# MOSFET_Board.net
KiCad netlist of a schematic drawn in EAGLE
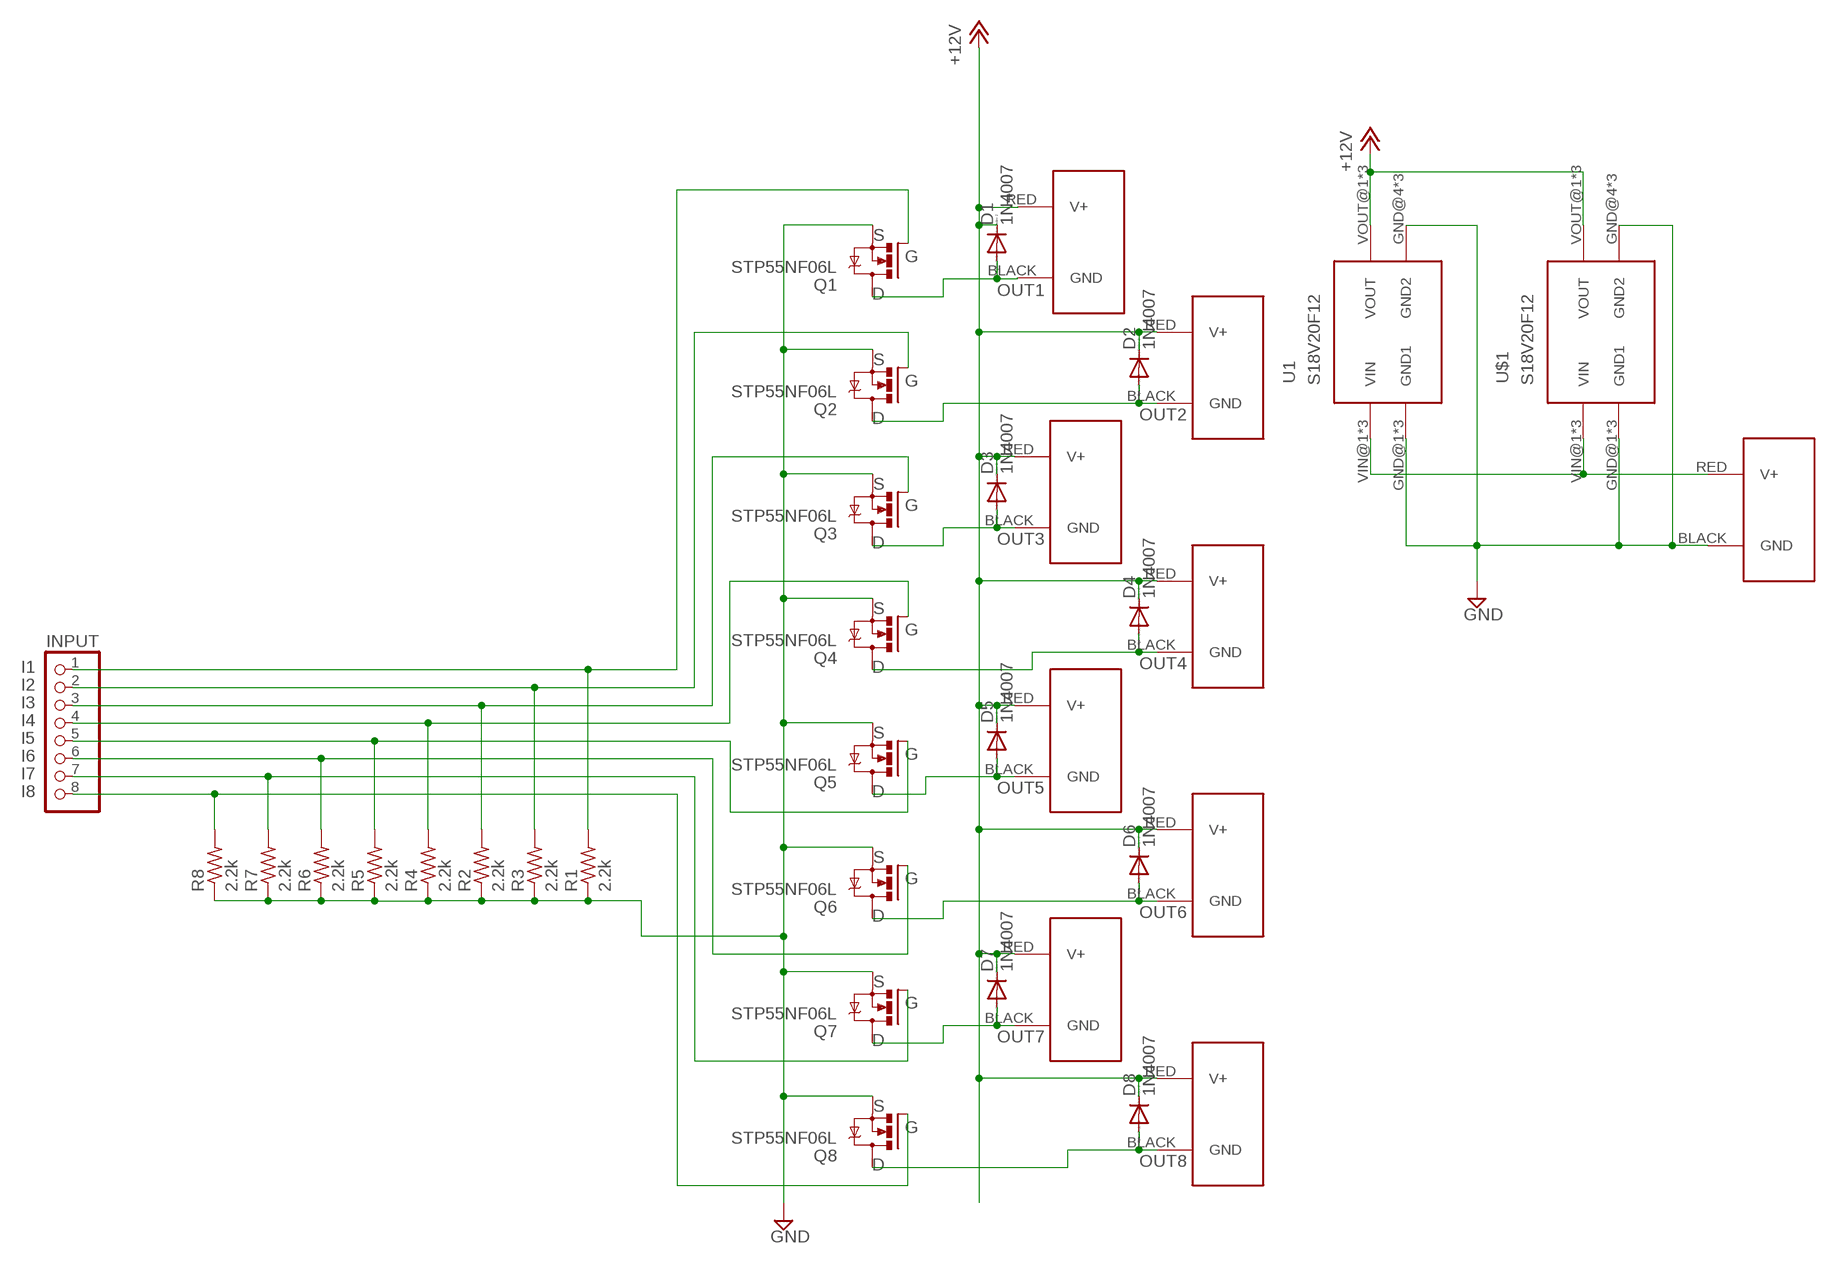
[diagram p0: schematic, sheet 1]

(export (version "E")
  (design (tool "Eeschema 10.0.6"))
  (components
    (comp (ref "D1")
      (value "1N4007")
      (footprint "eagle-import:DO41-10")
      (libsource (lib "eagle-import") (part "1N4007"))
    )
    (comp (ref "D2")
      (value "1N4007")
      (footprint "eagle-import:DO41-10")
      (libsource (lib "eagle-import") (part "1N4007"))
    )
    (comp (ref "D3")
      (value "1N4007")
      (footprint "eagle-import:DO41-10")
      (libsource (lib "eagle-import") (part "1N4007"))
    )
    (comp (ref "D4")
      (value "1N4007")
      (footprint "eagle-import:DO41-10")
      (libsource (lib "eagle-import") (part "1N4007"))
    )
    (comp (ref "D5")
      (value "1N4007")
      (footprint "eagle-import:DO41-10")
      (libsource (lib "eagle-import") (part "1N4007"))
    )
    (comp (ref "D6")
      (value "1N4007")
      (footprint "eagle-import:DO41-10")
      (libsource (lib "eagle-import") (part "1N4007"))
    )
    (comp (ref "D7")
      (value "1N4007")
      (footprint "eagle-import:DO41-10")
      (libsource (lib "eagle-import") (part "1N4007"))
    )
    (comp (ref "D8")
      (value "1N4007")
      (footprint "eagle-import:DO41-10")
      (libsource (lib "eagle-import") (part "1N4007"))
    )
    (comp (ref "INPUT")
      (value "PINHD-1X8")
      (footprint "eagle-import:1X08")
      (libsource (lib "eagle-import") (part "PINHD-1X8"))
    )
    (comp (ref "J1")
      (value "POWERPOLE_POWER25A")
      (footprint "eagle-import:POWERPOLE_PAIR_25A")
      (libsource (lib "eagle-import") (part "POWERPOLE_POWER25A"))
    )
    (comp (ref "J2")
      (value "POWERPOLE_POWER25A")
      (footprint "eagle-import:POWERPOLE_PAIR_25A")
      (libsource (lib "eagle-import") (part "POWERPOLE_POWER25A"))
    )
    (comp (ref "J3")
      (value "POWERPOLE_POWER25A")
      (footprint "eagle-import:POWERPOLE_PAIR_25A")
      (libsource (lib "eagle-import") (part "POWERPOLE_POWER25A"))
    )
    (comp (ref "J4")
      (value "POWERPOLE_POWER25A")
      (footprint "eagle-import:POWERPOLE_PAIR_25A")
      (libsource (lib "eagle-import") (part "POWERPOLE_POWER25A"))
    )
    (comp (ref "J5")
      (value "POWERPOLE_POWER25A")
      (footprint "eagle-import:POWERPOLE_PAIR_25A")
      (libsource (lib "eagle-import") (part "POWERPOLE_POWER25A"))
    )
    (comp (ref "J6")
      (value "POWERPOLE_POWER25A")
      (footprint "eagle-import:POWERPOLE_PAIR_25A")
      (libsource (lib "eagle-import") (part "POWERPOLE_POWER25A"))
    )
    (comp (ref "J7")
      (value "POWERPOLE_POWER25A")
      (footprint "eagle-import:POWERPOLE_PAIR_25A")
      (libsource (lib "eagle-import") (part "POWERPOLE_POWER25A"))
    )
    (comp (ref "J8")
      (value "POWERPOLE_POWER25A")
      (footprint "eagle-import:POWERPOLE_PAIR_25A")
      (libsource (lib "eagle-import") (part "POWERPOLE_POWER25A"))
    )
    (comp (ref "J9")
      (value "POWERPOLE_POWER25A")
      (footprint "eagle-import:POWERPOLE_PAIR_25A")
      (libsource (lib "eagle-import") (part "POWERPOLE_POWER25A"))
    )
    (comp (ref "Q1")
      (value "STP55NF06L")
      (footprint "eagle-import:TO220-3")
      (libsource (lib "eagle-import") (part "STP55NF06L"))
    )
    (comp (ref "Q2")
      (value "STP55NF06L")
      (footprint "eagle-import:TO220-3")
      (libsource (lib "eagle-import") (part "STP55NF06L"))
    )
    (comp (ref "Q3")
      (value "STP55NF06L")
      (footprint "eagle-import:TO220-3")
      (libsource (lib "eagle-import") (part "STP55NF06L"))
    )
    (comp (ref "Q4")
      (value "STP55NF06L")
      (footprint "eagle-import:TO220-3")
      (libsource (lib "eagle-import") (part "STP55NF06L"))
    )
    (comp (ref "Q5")
      (value "STP55NF06L")
      (footprint "eagle-import:TO220-3")
      (libsource (lib "eagle-import") (part "STP55NF06L"))
    )
    (comp (ref "Q6")
      (value "STP55NF06L")
      (footprint "eagle-import:TO220-3")
      (libsource (lib "eagle-import") (part "STP55NF06L"))
    )
    (comp (ref "Q7")
      (value "STP55NF06L")
      (footprint "eagle-import:TO220-3")
      (libsource (lib "eagle-import") (part "STP55NF06L"))
    )
    (comp (ref "Q8")
      (value "STP55NF06L")
      (footprint "eagle-import:TO220-3")
      (libsource (lib "eagle-import") (part "STP55NF06L"))
    )
    (comp (ref "R1")
      (value "2.2k")
      (footprint "eagle-import:0207_10")
      (libsource (lib "eagle-import") (part "R-US_0207/10"))
    )
    (comp (ref "R2")
      (value "2.2k")
      (footprint "eagle-import:0207_10")
      (libsource (lib "eagle-import") (part "R-US_0207/10"))
    )
    (comp (ref "R3")
      (value "2.2k")
      (footprint "eagle-import:0207_10")
      (libsource (lib "eagle-import") (part "R-US_0207/10"))
    )
    (comp (ref "R4")
      (value "2.2k")
      (footprint "eagle-import:0207_10")
      (libsource (lib "eagle-import") (part "R-US_0207/10"))
    )
    (comp (ref "R5")
      (value "2.2k")
      (footprint "eagle-import:0207_10")
      (libsource (lib "eagle-import") (part "R-US_0207/10"))
    )
    (comp (ref "R6")
      (value "2.2k")
      (footprint "eagle-import:0207_10")
      (libsource (lib "eagle-import") (part "R-US_0207/10"))
    )
    (comp (ref "R7")
      (value "2.2k")
      (footprint "eagle-import:0207_10")
      (libsource (lib "eagle-import") (part "R-US_0207/10"))
    )
    (comp (ref "R8")
      (value "2.2k")
      (footprint "eagle-import:0207_10")
      (libsource (lib "eagle-import") (part "R-US_0207/10"))
    )
    (comp (ref "U$1")
      (value "S18V20F12")
      (footprint "eagle-import:S18V20")
      (libsource (lib "eagle-import") (part "S18V20F12"))
    )
    (comp (ref "U1")
      (value "S18V20F12")
      (footprint "eagle-import:S18V20")
      (libsource (lib "eagle-import") (part "S18V20F12"))
    )
  )
  (nets
    (net (code "1") (name "+12V") (class "Default")
      (node (ref "D1") (pin "C") (pinfunction "C_C") (pintype "passive"))
      (node (ref "D2") (pin "C") (pinfunction "C_C") (pintype "passive"))
      (node (ref "D3") (pin "C") (pinfunction "C_C") (pintype "passive"))
      (node (ref "D4") (pin "C") (pinfunction "C_C") (pintype "passive"))
      (node (ref "D5") (pin "C") (pinfunction "C_C") (pintype "passive"))
      (node (ref "D6") (pin "C") (pinfunction "C_C") (pintype "passive"))
      (node (ref "D7") (pin "C") (pinfunction "C_C") (pintype "passive"))
      (node (ref "D8") (pin "C") (pinfunction "C_C") (pintype "passive"))
      (node (ref "J2") (pin "RED") (pinfunction "V+_RED") (pintype "power_in"))
      (node (ref "J3") (pin "RED") (pinfunction "V+_RED") (pintype "power_in"))
      (node (ref "J4") (pin "RED") (pinfunction "V+_RED") (pintype "power_in"))
      (node (ref "J5") (pin "RED") (pinfunction "V+_RED") (pintype "power_in"))
      (node (ref "J6") (pin "RED") (pinfunction "V+_RED") (pintype "power_in"))
      (node (ref "J7") (pin "RED") (pinfunction "V+_RED") (pintype "power_in"))
      (node (ref "J8") (pin "RED") (pinfunction "V+_RED") (pintype "power_in"))
      (node (ref "J9") (pin "RED") (pinfunction "V+_RED") (pintype "power_in"))
      (node (ref "U$1") (pin "VOUT@1") (pinfunction "VOUT_VOUT@1") (pintype "power_in"))
      (node (ref "U$1") (pin "VOUT@2") (pinfunction "VOUT_VOUT@2") (pintype "power_in"))
      (node (ref "U$1") (pin "VOUT@3") (pinfunction "VOUT_VOUT@3") (pintype "power_in"))
      (node (ref "U1") (pin "VOUT@1") (pinfunction "VOUT_VOUT@1") (pintype "power_in"))
      (node (ref "U1") (pin "VOUT@2") (pinfunction "VOUT_VOUT@2") (pintype "power_in"))
      (node (ref "U1") (pin "VOUT@3") (pinfunction "VOUT_VOUT@3") (pintype "power_in"))
    )
    (net (code "2") (name "/I1") (class "Default")
      (node (ref "INPUT") (pin "1") (pinfunction "1_1") (pintype "passive"))
      (node (ref "Q1") (pin "G") (pinfunction "G_G") (pintype "passive"))
      (node (ref "R1") (pin "2") (pinfunction "2_2") (pintype "passive"))
    )
    (net (code "3") (name "/I2") (class "Default")
      (node (ref "INPUT") (pin "2") (pinfunction "2_2") (pintype "passive"))
      (node (ref "Q2") (pin "G") (pinfunction "G_G") (pintype "passive"))
      (node (ref "R3") (pin "2") (pinfunction "2_2") (pintype "passive"))
    )
    (net (code "4") (name "/I3") (class "Default")
      (node (ref "INPUT") (pin "3") (pinfunction "3_3") (pintype "passive"))
      (node (ref "Q3") (pin "G") (pinfunction "G_G") (pintype "passive"))
      (node (ref "R2") (pin "2") (pinfunction "2_2") (pintype "passive"))
    )
    (net (code "5") (name "/I4") (class "Default")
      (node (ref "INPUT") (pin "4") (pinfunction "4_4") (pintype "passive"))
      (node (ref "Q4") (pin "G") (pinfunction "G_G") (pintype "passive"))
      (node (ref "R4") (pin "2") (pinfunction "2_2") (pintype "passive"))
    )
    (net (code "6") (name "/I5") (class "Default")
      (node (ref "INPUT") (pin "5") (pinfunction "5_5") (pintype "passive"))
      (node (ref "Q5") (pin "G") (pinfunction "G_G") (pintype "passive"))
      (node (ref "R5") (pin "2") (pinfunction "2_2") (pintype "passive"))
    )
    (net (code "7") (name "/I6") (class "Default")
      (node (ref "INPUT") (pin "6") (pinfunction "6_6") (pintype "passive"))
      (node (ref "Q6") (pin "G") (pinfunction "G_G") (pintype "passive"))
      (node (ref "R6") (pin "2") (pinfunction "2_2") (pintype "passive"))
    )
    (net (code "8") (name "/I7") (class "Default")
      (node (ref "INPUT") (pin "7") (pinfunction "7_7") (pintype "passive"))
      (node (ref "Q7") (pin "G") (pinfunction "G_G") (pintype "passive"))
      (node (ref "R7") (pin "2") (pinfunction "2_2") (pintype "passive"))
    )
    (net (code "9") (name "/I8") (class "Default")
      (node (ref "INPUT") (pin "8") (pinfunction "8_8") (pintype "passive"))
      (node (ref "Q8") (pin "G") (pinfunction "G_G") (pintype "passive"))
      (node (ref "R8") (pin "2") (pinfunction "2_2") (pintype "passive"))
    )
    (net (code "10") (name "/OUT1") (class "Default")
      (node (ref "D1") (pin "A") (pinfunction "A_A") (pintype "passive"))
      (node (ref "J2") (pin "BLACK") (pinfunction "GND_BLACK") (pintype "power_in"))
      (node (ref "Q1") (pin "D") (pinfunction "D_D") (pintype "passive"))
    )
    (net (code "11") (name "/OUT2") (class "Default")
      (node (ref "D2") (pin "A") (pinfunction "A_A") (pintype "passive"))
      (node (ref "J3") (pin "BLACK") (pinfunction "GND_BLACK") (pintype "power_in"))
      (node (ref "Q2") (pin "D") (pinfunction "D_D") (pintype "passive"))
    )
    (net (code "12") (name "/OUT3") (class "Default")
      (node (ref "D3") (pin "A") (pinfunction "A_A") (pintype "passive"))
      (node (ref "J4") (pin "BLACK") (pinfunction "GND_BLACK") (pintype "power_in"))
      (node (ref "Q3") (pin "D") (pinfunction "D_D") (pintype "passive"))
    )
    (net (code "13") (name "/OUT4") (class "Default")
      (node (ref "D4") (pin "A") (pinfunction "A_A") (pintype "passive"))
      (node (ref "J5") (pin "BLACK") (pinfunction "GND_BLACK") (pintype "power_in"))
      (node (ref "Q4") (pin "D") (pinfunction "D_D") (pintype "passive"))
    )
    (net (code "14") (name "/OUT5") (class "Default")
      (node (ref "D5") (pin "A") (pinfunction "A_A") (pintype "passive"))
      (node (ref "J6") (pin "BLACK") (pinfunction "GND_BLACK") (pintype "power_in"))
      (node (ref "Q5") (pin "D") (pinfunction "D_D") (pintype "passive"))
    )
    (net (code "15") (name "/OUT6") (class "Default")
      (node (ref "D6") (pin "A") (pinfunction "A_A") (pintype "passive"))
      (node (ref "J7") (pin "BLACK") (pinfunction "GND_BLACK") (pintype "power_in"))
      (node (ref "Q6") (pin "D") (pinfunction "D_D") (pintype "passive"))
    )
    (net (code "16") (name "/OUT7") (class "Default")
      (node (ref "D7") (pin "A") (pinfunction "A_A") (pintype "passive"))
      (node (ref "J8") (pin "BLACK") (pinfunction "GND_BLACK") (pintype "power_in"))
      (node (ref "Q7") (pin "D") (pinfunction "D_D") (pintype "passive"))
    )
    (net (code "17") (name "/OUT8") (class "Default")
      (node (ref "D8") (pin "A") (pinfunction "A_A") (pintype "passive"))
      (node (ref "J9") (pin "BLACK") (pinfunction "GND_BLACK") (pintype "power_in"))
      (node (ref "Q8") (pin "D") (pinfunction "D_D") (pintype "passive"))
    )
    (net (code "18") (name "GND") (class "Default")
      (node (ref "J1") (pin "BLACK") (pinfunction "GND_BLACK") (pintype "power_in"))
      (node (ref "Q1") (pin "S") (pinfunction "S_S") (pintype "passive"))
      (node (ref "Q2") (pin "S") (pinfunction "S_S") (pintype "passive"))
      (node (ref "Q3") (pin "S") (pinfunction "S_S") (pintype "passive"))
      (node (ref "Q4") (pin "S") (pinfunction "S_S") (pintype "passive"))
      (node (ref "Q5") (pin "S") (pinfunction "S_S") (pintype "passive"))
      (node (ref "Q6") (pin "S") (pinfunction "S_S") (pintype "passive"))
      (node (ref "Q7") (pin "S") (pinfunction "S_S") (pintype "passive"))
      (node (ref "Q8") (pin "S") (pinfunction "S_S") (pintype "passive"))
      (node (ref "R1") (pin "1") (pinfunction "1_1") (pintype "passive"))
      (node (ref "R2") (pin "1") (pinfunction "1_1") (pintype "passive"))
      (node (ref "R3") (pin "1") (pinfunction "1_1") (pintype "passive"))
      (node (ref "R4") (pin "1") (pinfunction "1_1") (pintype "passive"))
      (node (ref "R5") (pin "1") (pinfunction "1_1") (pintype "passive"))
      (node (ref "R6") (pin "1") (pinfunction "1_1") (pintype "passive"))
      (node (ref "R7") (pin "1") (pinfunction "1_1") (pintype "passive"))
      (node (ref "R8") (pin "1") (pinfunction "1_1") (pintype "passive"))
      (node (ref "U$1") (pin "GND@1") (pinfunction "GND1_GND@1") (pintype "power_in"))
      (node (ref "U$1") (pin "GND@2") (pinfunction "GND1_GND@2") (pintype "power_in"))
      (node (ref "U$1") (pin "GND@3") (pinfunction "GND1_GND@3") (pintype "power_in"))
      (node (ref "U$1") (pin "GND@4") (pinfunction "GND2_GND@4") (pintype "power_in"))
      (node (ref "U$1") (pin "GND@5") (pinfunction "GND2_GND@5") (pintype "power_in"))
      (node (ref "U$1") (pin "GND@6") (pinfunction "GND2_GND@6") (pintype "power_in"))
      (node (ref "U1") (pin "GND@1") (pinfunction "GND1_GND@1") (pintype "power_in"))
      (node (ref "U1") (pin "GND@2") (pinfunction "GND1_GND@2") (pintype "power_in"))
      (node (ref "U1") (pin "GND@3") (pinfunction "GND1_GND@3") (pintype "power_in"))
      (node (ref "U1") (pin "GND@4") (pinfunction "GND2_GND@4") (pintype "power_in"))
      (node (ref "U1") (pin "GND@5") (pinfunction "GND2_GND@5") (pintype "power_in"))
      (node (ref "U1") (pin "GND@6") (pinfunction "GND2_GND@6") (pintype "power_in"))
    )
    (net (code "19") (name "Net-(J1-V+)") (class "Default")
      (node (ref "J1") (pin "RED") (pinfunction "V+_RED") (pintype "power_in"))
      (node (ref "U$1") (pin "VIN@1") (pinfunction "VIN_VIN@1") (pintype "power_in"))
      (node (ref "U$1") (pin "VIN@2") (pinfunction "VIN_VIN@2") (pintype "power_in"))
      (node (ref "U$1") (pin "VIN@3") (pinfunction "VIN_VIN@3") (pintype "power_in"))
      (node (ref "U1") (pin "VIN@1") (pinfunction "VIN_VIN@1") (pintype "power_in"))
      (node (ref "U1") (pin "VIN@2") (pinfunction "VIN_VIN@2") (pintype "power_in"))
      (node (ref "U1") (pin "VIN@3") (pinfunction "VIN_VIN@3") (pintype "power_in"))
    )
  )
)
